# uo_C_SE_Display_Module.net
KiCad netlist of a schematic drawn in EAGLE
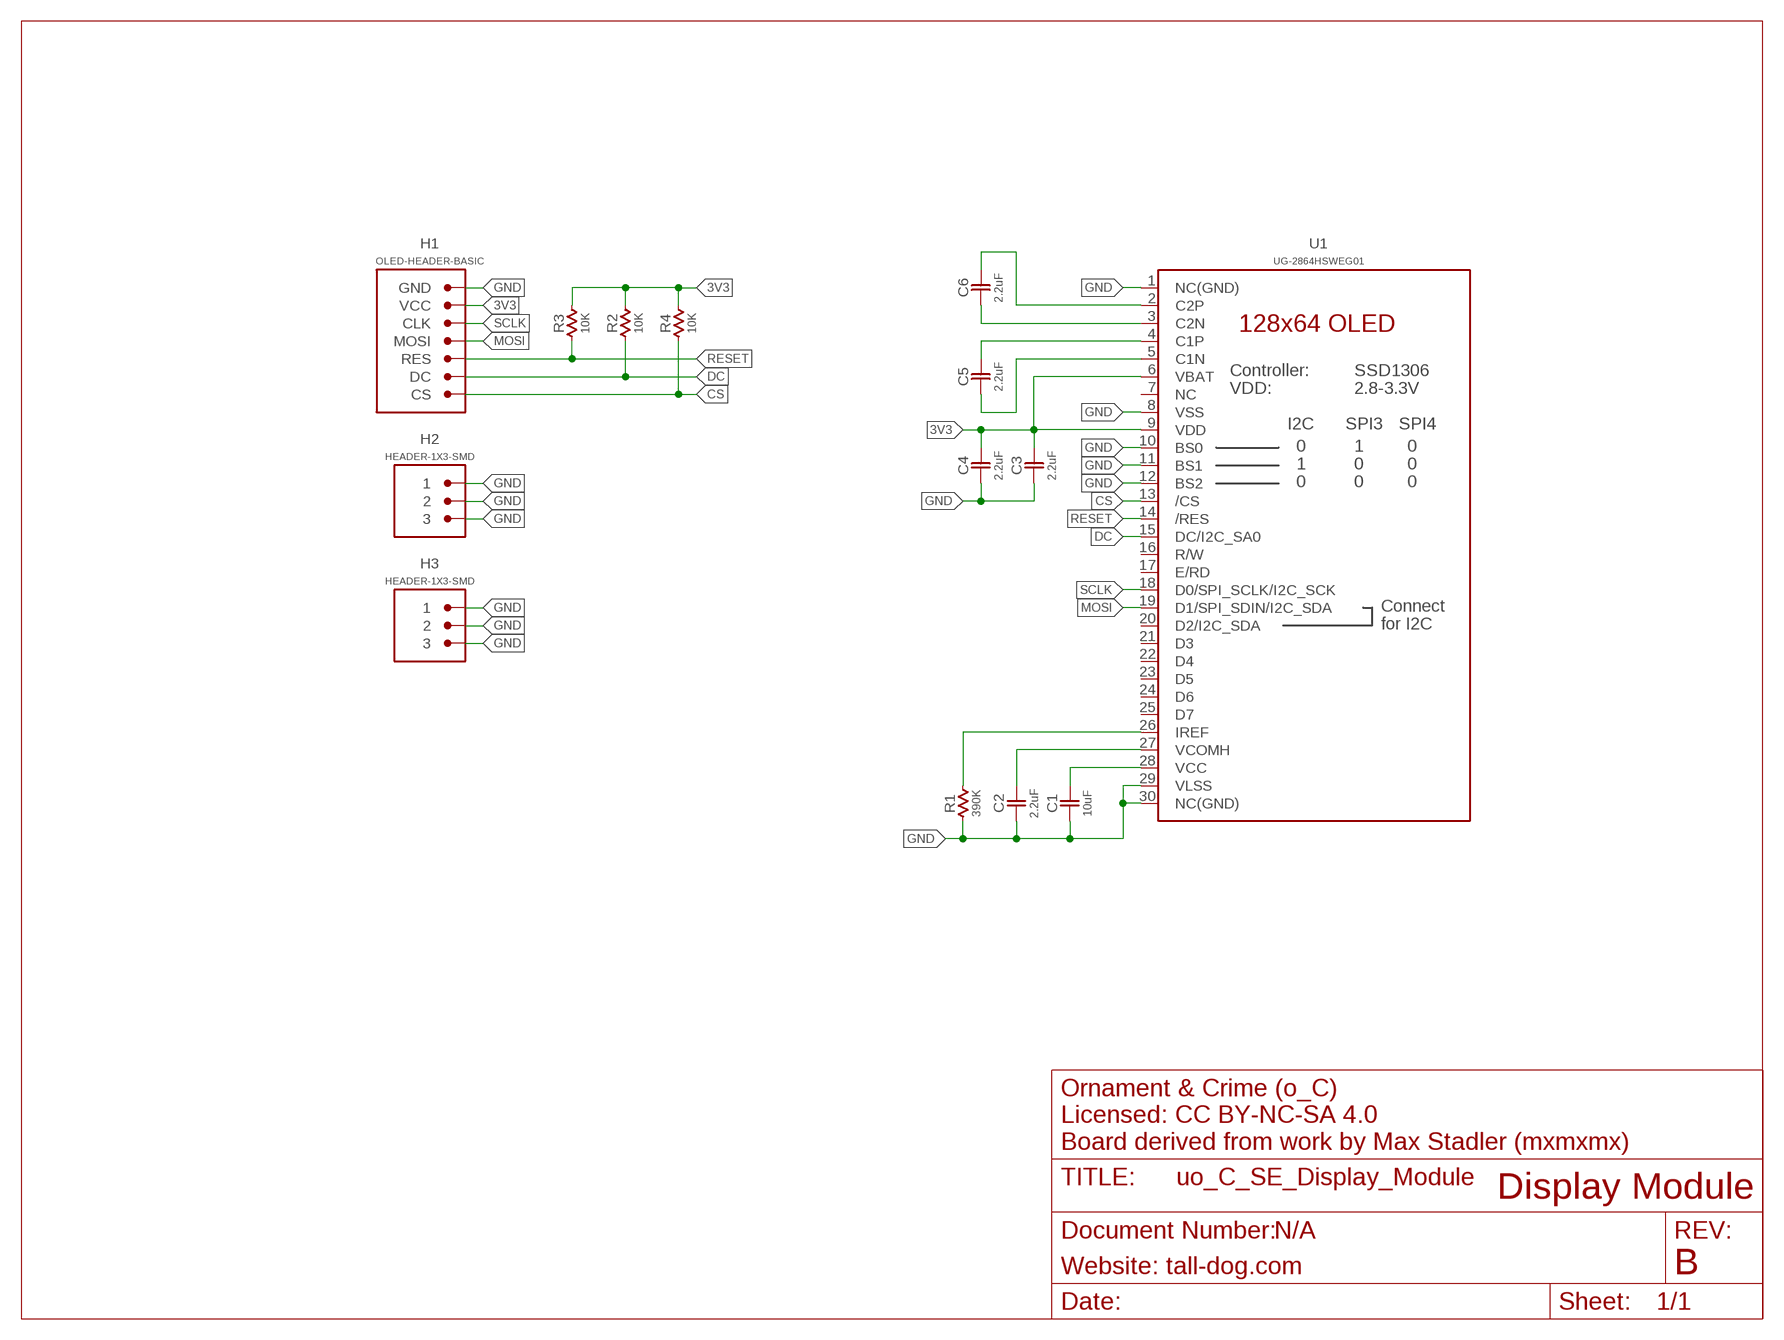
[diagram p0: schematic, sheet 1]

(export (version "E")
  (design (tool "Eeschema 10.0.6"))
  (components
    (comp (ref "C1")
      (value "10uF")
      (footprint "eagle-import:0805-NP")
      (libsource (lib "eagle-import") (part "CAP-NP-0805"))
    )
    (comp (ref "C2")
      (value "2.2uF")
      (footprint "eagle-import:0805-NP")
      (libsource (lib "eagle-import") (part "CAP-NP-0805"))
    )
    (comp (ref "C3")
      (value "2.2uF")
      (footprint "eagle-import:0805-NP")
      (libsource (lib "eagle-import") (part "CAP-NP-0805"))
    )
    (comp (ref "C4")
      (value "2.2uF")
      (footprint "eagle-import:0805-NP")
      (libsource (lib "eagle-import") (part "CAP-NP-0805"))
    )
    (comp (ref "C5")
      (value "2.2uF")
      (footprint "eagle-import:0805-NP")
      (libsource (lib "eagle-import") (part "CAP-NP-0805"))
    )
    (comp (ref "C6")
      (value "2.2uF")
      (footprint "eagle-import:0805-NP")
      (libsource (lib "eagle-import") (part "CAP-NP-0805"))
    )
    (comp (ref "H1")
      (value "OLED-HEADER-BASIC")
      (footprint "eagle-import:SMD-0.1-1X7")
      (libsource (lib "eagle-import") (part "OLED-HEADER-BASIC"))
    )
    (comp (ref "H2")
      (value "HEADER-1X3-SMD")
      (footprint "eagle-import:SMD-0.1-1X3")
      (libsource (lib "eagle-import") (part "HEADER-1X3-SMD"))
    )
    (comp (ref "H3")
      (value "HEADER-1X3-SMD")
      (footprint "eagle-import:SMD-0.1-1X3")
      (libsource (lib "eagle-import") (part "HEADER-1X3-SMD"))
    )
    (comp (ref "R1")
      (value "390K")
      (footprint "eagle-import:0805-NP")
      (libsource (lib "eagle-import") (part "RESISTOR-0805"))
    )
    (comp (ref "R2")
      (value "10K")
      (footprint "eagle-import:0805-NP")
      (libsource (lib "eagle-import") (part "RESISTOR-0805"))
    )
    (comp (ref "R3")
      (value "10K")
      (footprint "eagle-import:0805-NP")
      (libsource (lib "eagle-import") (part "RESISTOR-0805"))
    )
    (comp (ref "R4")
      (value "10K")
      (footprint "eagle-import:0805-NP")
      (libsource (lib "eagle-import") (part "RESISTOR-0805"))
    )
    (comp (ref "U1")
      (value "UG-2864HSWEG01")
      (footprint "eagle-import:OLED-128X64")
      (libsource (lib "eagle-import") (part "OLED-128X64"))
    )
  )
  (nets
    (net (code "1") (name "3V3") (class "Default")
      (node (ref "C3") (pin "2") (pinfunction "P$2_2") (pintype "bidirectional"))
      (node (ref "C4") (pin "2") (pinfunction "P$2_2") (pintype "bidirectional"))
      (node (ref "H1") (pin "2") (pinfunction "VCC_2") (pintype "bidirectional"))
      (node (ref "R2") (pin "2") (pinfunction "2_2") (pintype "passive"))
      (node (ref "R3") (pin "2") (pinfunction "2_2") (pintype "passive"))
      (node (ref "R4") (pin "2") (pinfunction "2_2") (pintype "passive"))
      (node (ref "U1") (pin "6") (pinfunction "VBAT_6") (pintype "input"))
      (node (ref "U1") (pin "9") (pinfunction "VDD_9") (pintype "power_in"))
    )
    (net (code "2") (name "CS") (class "Default")
      (node (ref "H1") (pin "7") (pinfunction "CS_7") (pintype "bidirectional"))
      (node (ref "R4") (pin "1") (pinfunction "1_1") (pintype "passive"))
      (node (ref "U1") (pin "13") (pinfunction "/CS_13") (pintype "input"))
    )
    (net (code "3") (name "DC") (class "Default")
      (node (ref "H1") (pin "6") (pinfunction "DC_6") (pintype "bidirectional"))
      (node (ref "R2") (pin "1") (pinfunction "1_1") (pintype "passive"))
      (node (ref "U1") (pin "15") (pinfunction "DC/I2C_SA0_15") (pintype "input"))
    )
    (net (code "4") (name "GND") (class "Default")
      (node (ref "C1") (pin "1") (pinfunction "P$1_1") (pintype "bidirectional"))
      (node (ref "C2") (pin "1") (pinfunction "P$1_1") (pintype "bidirectional"))
      (node (ref "C3") (pin "1") (pinfunction "P$1_1") (pintype "bidirectional"))
      (node (ref "C4") (pin "1") (pinfunction "P$1_1") (pintype "bidirectional"))
      (node (ref "H1") (pin "1") (pinfunction "GND_1") (pintype "bidirectional"))
      (node (ref "H2") (pin "1") (pinfunction "1_1") (pintype "bidirectional"))
      (node (ref "H2") (pin "2") (pinfunction "2_2") (pintype "bidirectional"))
      (node (ref "H2") (pin "3") (pinfunction "3_3") (pintype "bidirectional"))
      (node (ref "H3") (pin "1") (pinfunction "1_1") (pintype "bidirectional"))
      (node (ref "H3") (pin "2") (pinfunction "2_2") (pintype "bidirectional"))
      (node (ref "H3") (pin "3") (pinfunction "3_3") (pintype "bidirectional"))
      (node (ref "R1") (pin "1") (pinfunction "1_1") (pintype "passive"))
      (node (ref "U1") (pin "1") (pinfunction "NC(GND)_1") (pintype "input"))
      (node (ref "U1") (pin "10") (pinfunction "BS0_10") (pintype "input"))
      (node (ref "U1") (pin "11") (pinfunction "BS1_11") (pintype "input"))
      (node (ref "U1") (pin "12") (pinfunction "BS2_12") (pintype "input"))
      (node (ref "U1") (pin "29") (pinfunction "VLSS_29") (pintype "power_in"))
      (node (ref "U1") (pin "30") (pinfunction "NC(GND)_30") (pintype "input"))
      (node (ref "U1") (pin "8") (pinfunction "VSS_8") (pintype "power_in"))
    )
    (net (code "5") (name "MOSI") (class "Default")
      (node (ref "H1") (pin "4") (pinfunction "MOSI_4") (pintype "bidirectional"))
      (node (ref "U1") (pin "19") (pinfunction "D1/SPI_SDIN/I2C_SDA_19") (pintype "bidirectional"))
    )
    (net (code "6") (name "Net-(C1-P$2)") (class "Default")
      (node (ref "C1") (pin "2") (pinfunction "P$2_2") (pintype "bidirectional"))
      (node (ref "U1") (pin "28") (pinfunction "VCC_28") (pintype "power_in"))
    )
    (net (code "7") (name "Net-(C2-P$2)") (class "Default")
      (node (ref "C2") (pin "2") (pinfunction "P$2_2") (pintype "bidirectional"))
      (node (ref "U1") (pin "27") (pinfunction "VCOMH_27") (pintype "output"))
    )
    (net (code "8") (name "Net-(C5-P$1)") (class "Default")
      (node (ref "C5") (pin "1") (pinfunction "P$1_1") (pintype "bidirectional"))
      (node (ref "U1") (pin "5") (pinfunction "C1N_5") (pintype "input"))
    )
    (net (code "9") (name "Net-(C5-P$2)") (class "Default")
      (node (ref "C5") (pin "2") (pinfunction "P$2_2") (pintype "bidirectional"))
      (node (ref "U1") (pin "4") (pinfunction "C1P_4") (pintype "input"))
    )
    (net (code "10") (name "Net-(C6-P$1)") (class "Default")
      (node (ref "C6") (pin "1") (pinfunction "P$1_1") (pintype "bidirectional"))
      (node (ref "U1") (pin "3") (pinfunction "C2N_3") (pintype "input"))
    )
    (net (code "11") (name "Net-(C6-P$2)") (class "Default")
      (node (ref "C6") (pin "2") (pinfunction "P$2_2") (pintype "bidirectional"))
      (node (ref "U1") (pin "2") (pinfunction "C2P_2") (pintype "input"))
    )
    (net (code "12") (name "Net-(U1-IREF)") (class "Default")
      (node (ref "R1") (pin "2") (pinfunction "2_2") (pintype "passive"))
      (node (ref "U1") (pin "26") (pinfunction "IREF_26") (pintype "input"))
    )
    (net (code "13") (name "RESET") (class "Default")
      (node (ref "H1") (pin "5") (pinfunction "RES_5") (pintype "bidirectional"))
      (node (ref "R3") (pin "1") (pinfunction "1_1") (pintype "passive"))
      (node (ref "U1") (pin "14") (pinfunction "/RES_14") (pintype "input"))
    )
    (net (code "14") (name "SCLK") (class "Default")
      (node (ref "H1") (pin "3") (pinfunction "CLK_3") (pintype "bidirectional"))
      (node (ref "U1") (pin "18") (pinfunction "D0/SPI_SCLK/I2C_SCK_18") (pintype "bidirectional"))
    )
    (net (code "15") (name "unconnected-(U1-D2{slash}I2C_SDA-Pad20)") (class "Default")
      (node (ref "U1") (pin "20") (pinfunction "D2/I2C_SDA_20") (pintype "bidirectional"))
    )
    (net (code "16") (name "unconnected-(U1-D3-Pad21)") (class "Default")
      (node (ref "U1") (pin "21") (pinfunction "D3_21") (pintype "bidirectional"))
    )
    (net (code "17") (name "unconnected-(U1-D4-Pad22)") (class "Default")
      (node (ref "U1") (pin "22") (pinfunction "D4_22") (pintype "bidirectional"))
    )
    (net (code "18") (name "unconnected-(U1-D5-Pad23)") (class "Default")
      (node (ref "U1") (pin "23") (pinfunction "D5_23") (pintype "bidirectional"))
    )
    (net (code "19") (name "unconnected-(U1-D6-Pad24)") (class "Default")
      (node (ref "U1") (pin "24") (pinfunction "D6_24") (pintype "bidirectional"))
    )
    (net (code "20") (name "unconnected-(U1-D7-Pad25)") (class "Default")
      (node (ref "U1") (pin "25") (pinfunction "D7_25") (pintype "bidirectional"))
    )
    (net (code "21") (name "unconnected-(U1-E{slash}RD-Pad17)") (class "Default")
      (node (ref "U1") (pin "17") (pinfunction "E/RD_17") (pintype "input"))
    )
    (net (code "22") (name "unconnected-(U1-NC-Pad7)") (class "Default")
      (node (ref "U1") (pin "7") (pinfunction "NC_7") (pintype "no_connect"))
    )
    (net (code "23") (name "unconnected-(U1-R{slash}W-Pad16)") (class "Default")
      (node (ref "U1") (pin "16") (pinfunction "R/W_16") (pintype "input"))
    )
  )
)
